# JacdacMicroBitShieldLPEc_113.net
KiCad netlist of a schematic drawn in Altium Designer
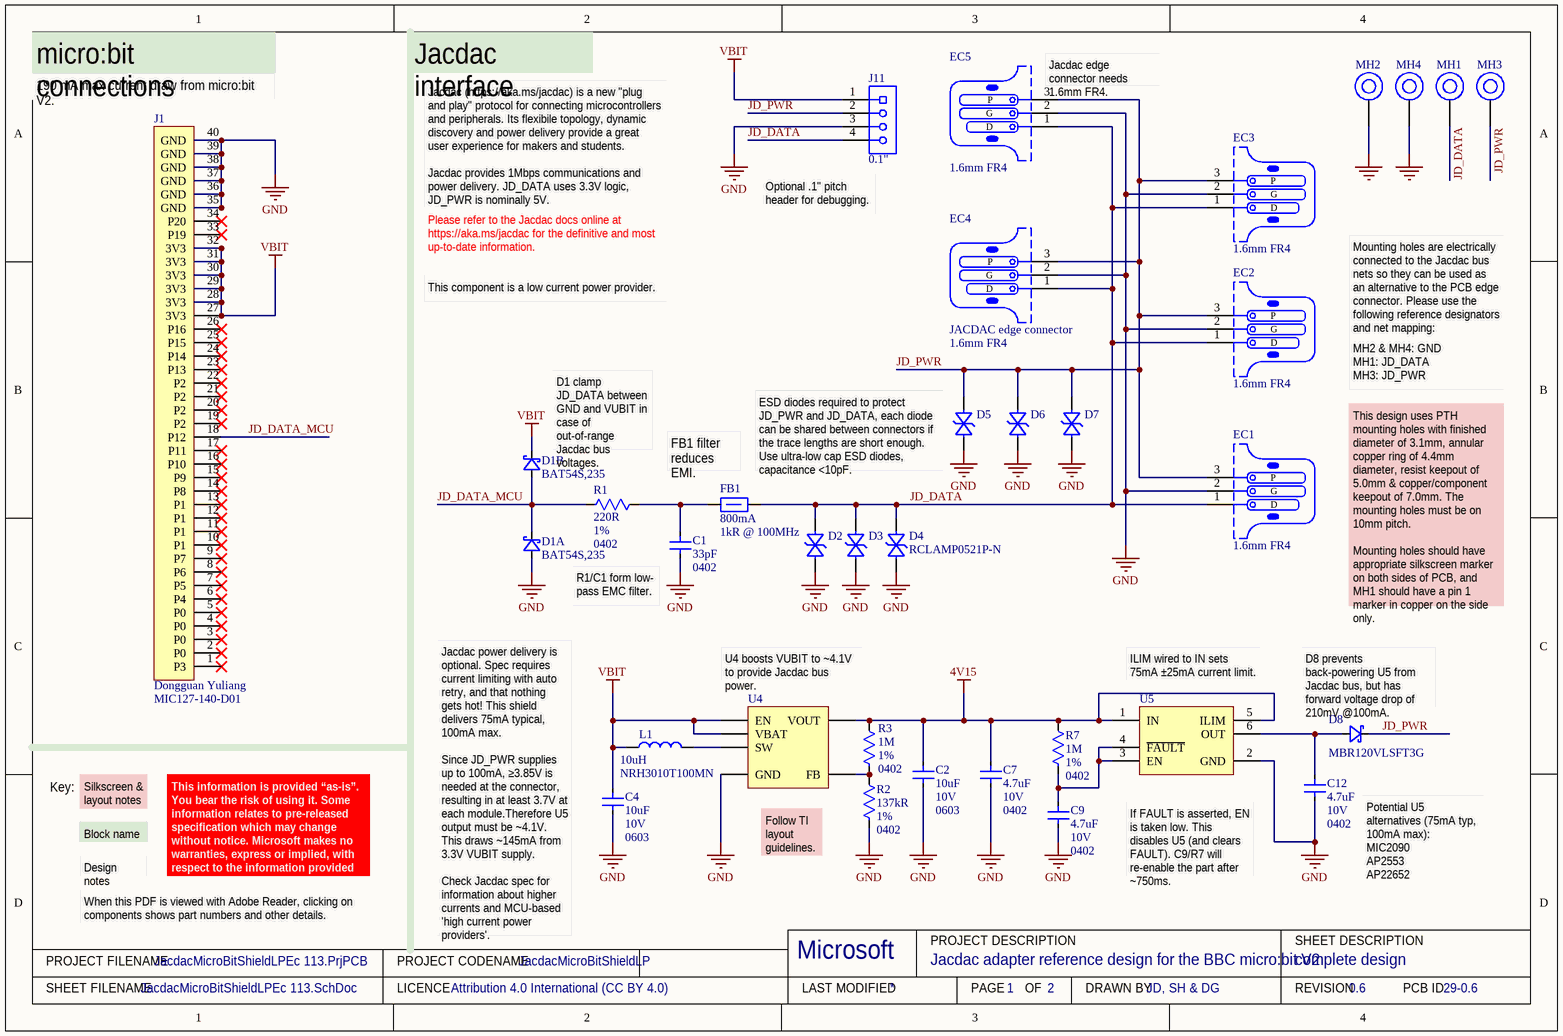
[diagram p0: JacdacMicroBitShieldLPEc 113.SchDoc]

(export (version "E")
  (design (tool "Eeschema 10.0.6"))
  (components
    (comp (ref "C1")
      (value "CL05C330JB51PNC")
      (footprint "C0402_0.55MM - without outline")
      (description "CAP CER 33PF 50V NP0 0402")
      (fields
        (field (name "MANUFACTURER") "Samsung")
        (field (name "TOLERANCE") "5%")
        (field (name "CAPACITANCE") "33pF")
        (field (name "CASE CODE (IMPERIAL)") "0402")
        (field (name "CHECKED") "?")
        (field (name "CREATED") "DG")
      )
      (libsource (lib "Samsung") (part "CL05C330JB51PNC"))
    )
    (comp (ref "C2")
      (value "CL10A106KP8NNNC")
      (footprint "C0603 - without outline")
      (description "CAP CER 10UF 10V X5R 0603")
      (fields
        (field (name "MANUFACTURER") "Samsung")
        (field (name "TOLERANCE") "10%")
        (field (name "CAPACITANCE") "10uF")
        (field (name "VOLTAGE RATING") "10V")
        (field (name "CASE CODE (IMPERIAL)") "0603")
      )
      (libsource (lib "Samsung") (part "CL10A106KP8NNNC"))
    )
    (comp (ref "C4")
      (value "CL10A106KP8NNNC")
      (footprint "C0603 - without outline")
      (description "CAP CER 10UF 10V X5R 0603")
      (fields
        (field (name "MANUFACTURER") "Samsung")
        (field (name "TOLERANCE") "10%")
        (field (name "CAPACITANCE") "10uF")
        (field (name "VOLTAGE RATING") "10V")
        (field (name "CASE CODE (IMPERIAL)") "0603")
      )
      (libsource (lib "Samsung") (part "CL10A106KP8NNNC"))
    )
    (comp (ref "C7")
      (value "CL05A475MP5NRNC")
      (footprint "R0402 - Without outline")
      (description "CAP CER 4.7UF 10V X5R 0402")
      (fields
        (field (name "MANUFACTURER") "Samsung")
        (field (name "TOLERANCE") "20%")
        (field (name "CAPACITANCE") "4.7uF")
        (field (name "VOLTAGE RATING") "10V")
        (field (name "CASE CODE (IMPERIAL)") "0402")
        (field (name "CREATED BY") "D. Gakure")
        (field (name "CHECKED BY") "?")
      )
      (libsource (lib "Samsung") (part "CL05A475MP5NRNC"))
    )
    (comp (ref "C9")
      (value "CL05A475MP5NRNC")
      (footprint "R0402 - Without outline")
      (description "CAP CER 4.7UF 10V X5R 0402")
      (fields
        (field (name "MANUFACTURER") "Samsung")
        (field (name "TOLERANCE") "20%")
        (field (name "CAPACITANCE") "4.7uF")
        (field (name "VOLTAGE RATING") "10V")
        (field (name "CASE CODE (IMPERIAL)") "0402")
        (field (name "CREATED BY") "D. Gakure")
        (field (name "CHECKED BY") "?")
      )
      (libsource (lib "Samsung") (part "CL05A475MP5NRNC"))
    )
    (comp (ref "C12")
      (value "CL05A475MP5NRNC")
      (footprint "R0402 - Without outline")
      (description "CAP CER 4.7UF 10V X5R 0402")
      (fields
        (field (name "MANUFACTURER") "Samsung")
        (field (name "TOLERANCE") "20%")
        (field (name "CAPACITANCE") "4.7uF")
        (field (name "VOLTAGE RATING") "10V")
        (field (name "CASE CODE (IMPERIAL)") "0402")
        (field (name "CREATED BY") "D. Gakure")
        (field (name "CHECKED BY") "?")
      )
      (libsource (lib "Samsung") (part "CL05A475MP5NRNC"))
    )
    (comp (ref "D1")
      (value "BAT54S")
      (footprint "NXP-BAT54S-TO-236AB - without outline")
      (description "DIODE ARRAY SCHOTTKY 30V SOT23")
      (fields (field (name "MANUFACTURER") "Nexperia") (field (name "MANUFACTURER PART NUMBER") "BAT54S,235"))
      (libsource (lib "NXP") (part "BAT54S"))
    )
    (comp (ref "D2")
      (value "RCLAMP0521P-N")
      (footprint "TVS 0402 - L")
      (description "Bidirectional 5V (Max) 6V 16V 3.5A (8/20us) 0402 TVS RoHS")
      (fields
        (field (name "MANUFACTURER") "Born Semiconductor")
        (field (name "CREATED BY") "D Gakure")
        (field (name "CHECKED BY") "?")
      )
      (libsource (lib "BornSemiconductor") (part "RCLAMP0521P-N"))
    )
    (comp (ref "D3")
      (value "RCLAMP0521P-N")
      (footprint "TVS 0402 - L")
      (description "Bidirectional 5V (Max) 6V 16V 3.5A (8/20us) 0402 TVS RoHS")
      (fields
        (field (name "MANUFACTURER") "Born Semiconductor")
        (field (name "CREATED BY") "D Gakure")
        (field (name "CHECKED BY") "?")
      )
      (libsource (lib "BornSemiconductor") (part "RCLAMP0521P-N"))
    )
    (comp (ref "D4")
      (value "RCLAMP0521P-N")
      (footprint "TVS 0402 - L")
      (description "Bidirectional 5V (Max) 6V 16V 3.5A (8/20us) 0402 TVS RoHS")
      (fields
        (field (name "MANUFACTURER") "Born Semiconductor")
        (field (name "MANUFACTURER PART NUMBER") "RCLAMP0521P-N")
        (field (name "CREATED BY") "D Gakure")
        (field (name "CHECKED BY") "?")
      )
      (libsource (lib "BornSemiconductor") (part "RCLAMP0521P-N"))
    )
    (comp (ref "D5")
      (value "RCLAMP0521P-N")
      (footprint "TVS 0402 - L")
      (description "Bidirectional 5V (Max) 6V 16V 3.5A (8/20us) 0402 TVS RoHS")
      (fields
        (field (name "MANUFACTURER") "Born Semiconductor")
        (field (name "CREATED BY") "D Gakure")
        (field (name "CHECKED BY") "?")
      )
      (libsource (lib "BornSemiconductor") (part "RCLAMP0521P-N"))
    )
    (comp (ref "D6")
      (value "RCLAMP0521P-N")
      (footprint "TVS 0402 - L")
      (description "Bidirectional 5V (Max) 6V 16V 3.5A (8/20us) 0402 TVS RoHS")
      (fields
        (field (name "MANUFACTURER") "Born Semiconductor")
        (field (name "CREATED BY") "D Gakure")
        (field (name "CHECKED BY") "?")
      )
      (libsource (lib "BornSemiconductor") (part "RCLAMP0521P-N"))
    )
    (comp (ref "D7")
      (value "RCLAMP0521P-N")
      (footprint "TVS 0402 - L")
      (description "Bidirectional 5V (Max) 6V 16V 3.5A (8/20us) 0402 TVS RoHS")
      (fields
        (field (name "MANUFACTURER") "Born Semiconductor")
        (field (name "CREATED BY") "D Gakure")
        (field (name "CHECKED BY") "?")
      )
      (libsource (lib "BornSemiconductor") (part "RCLAMP0521P-N"))
    )
    (comp (ref "D8")
      (value "MBR120VLSFT3G")
      (footprint "MBR120VLSFT3G")
      (description "DIODE SCHOTTKY 20V 1A SOD123FL")
      (fields
        (field (name "MANUFACTURER") "ON Semiconductor")
        (field (name "MANUFACTURER PART NUMBER") "MBR120VLSFT3G")
      )
      (libsource (lib "OnSemiconductor") (part "MBR120VLSFT3G"))
    )
    (comp (ref "EC1")
      (value "Jacdac edge connector")
      (footprint "JACDAC_edge_connector:JACDAC_EDGE_CONNECTOR_NO_TRACES")
      (description "3 pin jacdac edge connector 1.27mm pitch")
      (fields
        (field (name "MANUFACTURER PART NUMBER") "JACDAC_EDGE_CONNECTOR")
        (field (name "PCB TYPE") "1.6mm FR4")
        (field (name "CHECKED BY") "?")
        (field (name "CREATED BY") "D. Gakure")
      )
      (libsource (lib "generic-con") (part "Jacdac edge connector"))
    )
    (comp (ref "EC2")
      (value "Jacdac edge connector")
      (footprint "JACDAC_edge_connector:JACDAC_EDGE_CONNECTOR_NO_TRACES")
      (description "3 pin jacdac edge connector 1.27mm pitch")
      (fields
        (field (name "MANUFACTURER PART NUMBER") "JACDAC_EDGE_CONNECTOR")
        (field (name "PCB TYPE") "1.6mm FR4")
        (field (name "CHECKED BY") "?")
        (field (name "CREATED BY") "D. Gakure")
      )
      (libsource (lib "generic-con") (part "Jacdac edge connector"))
    )
    (comp (ref "EC3")
      (value "Jacdac edge connector")
      (footprint "JACDAC_edge_connector:JACDAC_EDGE_CONNECTOR_NO_TRACES")
      (description "3 pin jacdac edge connector 1.27mm pitch")
      (fields
        (field (name "MANUFACTURER PART NUMBER") "JACDAC_EDGE_CONNECTOR")
        (field (name "PCB TYPE") "1.6mm FR4")
        (field (name "CHECKED BY") "?")
        (field (name "CREATED BY") "D. Gakure")
      )
      (libsource (lib "generic-con") (part "Jacdac edge connector"))
    )
    (comp (ref "EC4")
      (value "JACDAC edge connector")
      (footprint "JACDAC_edge_connector:JACDAC_EDGE_CONNECTOR_NO_TRACES")
      (description "3 pin jacdac edge connector 1.27mm pitch")
      (fields
        (field (name "MANUFACTURER PART NUMBER") "JACDAC_EDGE_CONNECTOR")
        (field (name "PCB TYPE") "1.6mm FR4")
        (field (name "CHECKED BY") "?")
        (field (name "CREATED BY") "D. Gakure")
      )
      (libsource (lib "") (part "Jacdac edge connector_1"))
    )
    (comp (ref "EC5")
      (value "Jacdac edge connector")
      (footprint "JACDAC_edge_connector:JACDAC_EDGE_CONNECTOR_NO_TRACES")
      (description "3 pin jacdac edge connector 1.27mm pitch")
      (fields
        (field (name "MANUFACTURER PART NUMBER") "JACDAC_EDGE_CONNECTOR")
        (field (name "PCB TYPE") "1.6mm FR4")
        (field (name "CHECKED BY") "?")
        (field (name "CREATED BY") "D. Gakure")
      )
      (libsource (lib "") (part "Jacdac edge connector_1"))
    )
    (comp (ref "FB1")
      (value "TDK MPZ1608S102ATA00")
      (footprint "TDK MPZ1608 0.8mm - without outline")
      (description "0603 1k@100MHz 0.8A chip")
      (fields
        (field (name "TOLERANCE") "25%")
        (field (name "MANUFACTURER") "TDK")
        (field (name "CURRENT RATING") "800mA")
        (field (name "IMPEDANCE") "1kR @ 100MHz")
      )
      (libsource (lib "TDK") (part "TDK MPZ1608S102ATA00"))
    )
    (comp (ref "J1")
      (value "Planar 1x40p 1.27 mm pitch edge connector for the micro:bit")
      (footprint "MIC127-140-D01")
      (description "\"Same plane\" 1x40p 1.27mm Dongguan Yuliang BBC micro:bit edge connector")
      (fields
        (field (name "MANUFACTURER") "Dongguan Yuliang")
        (field (name "MANUFACTURER PART NUMBER") "MIC127-140-D01")
      )
      (libsource (lib "Yuliang") (part "MIC127-140-D01"))
    )
    (comp (ref "J11")
      (value "0.1\"")
      (footprint "Generic 1x4 2.54mm header")
      (description "2.54mm, 4x1 way, vertical, square pin, gold plate")
      (fields
        (field (name "MANUFACTURER") "Multicomp")
        (field (name "MANUFACTURER PART NUMBER") "2211S-04G")
        (field (name "CREATED BY") "HUGHWI")
      )
      (libsource (lib "generic-con") (part "Header Multicomp 2211S-04G-whitesch"))
    )
    (comp (ref "L1")
      (value "NRH3010T100MN")
      (footprint "NRH3010T100MN")
      (fields
        (field (name "TOLERANCE") "20%")
        (field (name "INDUCTANCE") "10uH")
        (field (name "MANUFACTURER") "Taiyo Yuden")
        (field (name "MANUFACTURER PART NUMBER") "NRH3010T100MN")
      )
      (libsource (lib "TaiyoYuden ") (part "NRH3010T100MN"))
    )
    (comp (ref "MH1")
      (value "MH_6.5MMK_4.5MMC_3.0MMD_PTH")
      (footprint "MH_6.5MMK_4.5MMC_3.0MMD_PTH:MH_6.5MMK_4.5MMC_3.0MMD_PTH")
      (description "Mounting Hole 6.5mm keepout, 4.5mm annualar ring and 3.0mm Drill PTH")
      (libsource (lib "generic") (part "MH_6.5MMK_4.5MMC_3.0MMD_PTH"))
    )
    (comp (ref "MH2")
      (value "MH_6.5MMK_4.5MMC_3.0MMD_PTH")
      (footprint "MH_6.5MMK_4.5MMC_3.0MMD_PTH:MH_6.5MMK_4.5MMC_3.0MMD_PTH")
      (description "Mounting Hole 6.5mm keepout, 4.5mm annualar ring and 3.0mm Drill PTH")
      (libsource (lib "generic") (part "MH_6.5MMK_4.5MMC_3.0MMD_PTH"))
    )
    (comp (ref "MH3")
      (value "MH_6.5MMK_4.5MMC_3.0MMD_PTH")
      (footprint "MH_6.5MMK_4.5MMC_3.0MMD_PTH:MH_6.5MMK_4.5MMC_3.0MMD_PTH")
      (description "Mounting Hole 6.5mm keepout, 4.5mm annualar ring and 3.0mm Drill PTH")
      (libsource (lib "generic") (part "MH_6.5MMK_4.5MMC_3.0MMD_PTH"))
    )
    (comp (ref "MH4")
      (value "MH_6.5MMK_4.5MMC_3.0MMD_PTH")
      (footprint "MH_6.5MMK_4.5MMC_3.0MMD_PTH:MH_6.5MMK_4.5MMC_3.0MMD_PTH")
      (description "Mounting Hole 6.5mm keepout, 4.5mm annualar ring and 3.0mm Drill PTH")
      (libsource (lib "generic") (part "MH_6.5MMK_4.5MMC_3.0MMD_PTH"))
    )
    (comp (ref "R1")
      (value "0402WGF2200TCE")
      (footprint "UNIROYAL-0402:R0402 - Without outline")
      (description "RES SMD 220 OHM 1% 1/16W 0402")
      (fields
        (field (name "MANUFACTURER") "Uniroyal Elec")
        (field (name "RESISTANCE") "220R")
        (field (name "TOLERANCE") "1%")
        (field (name "CASE CODE (IMPERIAL)") "0402")
      )
      (libsource (lib "UniroyalElec") (part "0402WGF2200TCE"))
    )
    (comp (ref "R2")
      (value "RC0402FR-07137KL")
      (footprint "R0402 - Without outline")
      (description "RES SMD 137K OHM 1% 1/16W 0402")
      (fields
        (field (name "MANUFACTURER") "Yageo")
        (field (name "RESISTANCE") "137kR")
        (field (name "TOLERANCE") "1%")
        (field (name "CASE CODE (IMPERIAL)") "0402")
      )
      (libsource (lib "Yageo") (part "RC0402FR-07137KL"))
    )
    (comp (ref "R3")
      (value "0402WGF1004TCE")
      (footprint "UNIROYAL-0402:R0402 - Without outline")
      (description "RES SMD 1M OHM 1% 1/16W 0402")
      (fields
        (field (name "MANUFACTURER") "Uniroyal Elec")
        (field (name "RESISTANCE") "1M")
        (field (name "TOLERANCE") "1%")
        (field (name "CASE CODE (IMPERIAL)") "0402")
      )
      (libsource (lib "UniroyalElec") (part "0402WGF1004TCE"))
    )
    (comp (ref "R7")
      (value "0402WGF1004TCE")
      (footprint "UNIROYAL-0402:R0402 - Without outline")
      (description "RES SMD 1M OHM 1% 1/16W 0402")
      (fields
        (field (name "MANUFACTURER") "Uniroyal Elec")
        (field (name "RESISTANCE") "1M")
        (field (name "TOLERANCE") "1%")
        (field (name "CASE CODE (IMPERIAL)") "0402")
      )
      (libsource (lib "UniroyalElec") (part "0402WGF1004TCE"))
    )
    (comp (ref "U4")
      (value "TLV61220")
      (footprint "TI-TLV61220 - without_outline")
      (description "IC REG BST ADJ 0.22A SYNC SOT23")
      (fields (field (name "MANUFACTURER PART NUMBER") "TLV61220DBVR"))
      (libsource (lib "TexasInstruments") (part "TLV61220"))
    )
    (comp (ref "U5")
      (value "TPS2553DBVR")
      (footprint "TI-TPS2553 - without_outline")
      (libsource (lib "TexasInstruments") (part "TPS2553DBVR"))
    )
  )
  (nets
    (net (code "1") (name "/JD_DATA") (class "Default")
      (node (ref "D2") (pin "1") (pinfunction "K_1") (pintype "passive"))
      (node (ref "D3") (pin "1") (pinfunction "K_1") (pintype "passive"))
      (node (ref "D4") (pin "1") (pinfunction "K_1") (pintype "passive"))
      (node (ref "EC1") (pin "1") (pinfunction "D_1") (pintype "passive"))
      (node (ref "EC2") (pin "1") (pinfunction "D_1") (pintype "passive"))
      (node (ref "EC3") (pin "1") (pinfunction "D_1") (pintype "passive"))
      (node (ref "EC4") (pin "1") (pinfunction "D_1") (pintype "passive"))
      (node (ref "EC5") (pin "1") (pinfunction "D_1") (pintype "passive"))
      (node (ref "FB1") (pin "1") (pinfunction "1_1") (pintype "passive"))
      (node (ref "J11") (pin "4") (pinfunction "4_4") (pintype "passive"))
      (node (ref "MH1") (pin "1") (pinfunction "1_1") (pintype "passive"))
    )
    (net (code "2") (name "/JD_DATA_MCU") (class "Default")
      (node (ref "D1") (pin "3") (pinfunction "K_3") (pintype "passive"))
      (node (ref "J1") (pin "18") (pinfunction "P12_18") (pintype "passive"))
      (node (ref "R1") (pin "1") (pinfunction "1_1") (pintype "passive"))
    )
    (net (code "3") (name "/JD_PWR") (class "Default")
      (node (ref "D5") (pin "1") (pinfunction "K_1") (pintype "passive"))
      (node (ref "D6") (pin "1") (pinfunction "K_1") (pintype "passive"))
      (node (ref "D7") (pin "1") (pinfunction "K_1") (pintype "passive"))
      (node (ref "D8") (pin "1") (pinfunction "K_1") (pintype "passive"))
      (node (ref "EC1") (pin "3") (pinfunction "P_3") (pintype "passive"))
      (node (ref "EC2") (pin "3") (pinfunction "P_3") (pintype "passive"))
      (node (ref "EC3") (pin "3") (pinfunction "P_3") (pintype "passive"))
      (node (ref "EC4") (pin "3") (pinfunction "P_3") (pintype "passive"))
      (node (ref "EC5") (pin "3") (pinfunction "P_3") (pintype "passive"))
      (node (ref "J11") (pin "2") (pinfunction "2_2") (pintype "passive"))
      (node (ref "MH3") (pin "1") (pinfunction "1_1") (pintype "passive"))
    )
    (net (code "4") (name "4V15") (class "Default")
      (node (ref "C2") (pin "2") (pinfunction "2_2") (pintype "passive"))
      (node (ref "C7") (pin "2") (pinfunction "2_2") (pintype "passive"))
      (node (ref "R3") (pin "2") (pinfunction "2_2") (pintype "passive"))
      (node (ref "R7") (pin "2") (pinfunction "2_2") (pintype "passive"))
      (node (ref "U4") (pin "5") (pinfunction "VOUT_5") (pintype "passive"))
      (node (ref "U5") (pin "1") (pinfunction "IN_1") (pintype "passive"))
      (node (ref "U5") (pin "5") (pinfunction "ILIM_5") (pintype "passive"))
    )
    (net (code "5") (name "GND") (class "Default")
      (node (ref "C1") (pin "1") (pinfunction "1_1") (pintype "passive"))
      (node (ref "C12") (pin "1") (pinfunction "1_1") (pintype "passive"))
      (node (ref "C2") (pin "1") (pinfunction "1_1") (pintype "passive"))
      (node (ref "C4") (pin "1") (pinfunction "1_1") (pintype "passive"))
      (node (ref "C7") (pin "1") (pinfunction "1_1") (pintype "passive"))
      (node (ref "C9") (pin "1") (pinfunction "1_1") (pintype "passive"))
      (node (ref "D1") (pin "1") (pinfunction "A_1") (pintype "passive"))
      (node (ref "D2") (pin "2") (pinfunction "A_2") (pintype "passive"))
      (node (ref "D3") (pin "2") (pinfunction "A_2") (pintype "passive"))
      (node (ref "D4") (pin "2") (pinfunction "A_2") (pintype "passive"))
      (node (ref "D5") (pin "2") (pinfunction "A_2") (pintype "passive"))
      (node (ref "D6") (pin "2") (pinfunction "A_2") (pintype "passive"))
      (node (ref "D7") (pin "2") (pinfunction "A_2") (pintype "passive"))
      (node (ref "EC1") (pin "2") (pinfunction "G_2") (pintype "passive"))
      (node (ref "EC2") (pin "2") (pinfunction "G_2") (pintype "passive"))
      (node (ref "EC3") (pin "2") (pinfunction "G_2") (pintype "passive"))
      (node (ref "EC4") (pin "2") (pinfunction "G_2") (pintype "passive"))
      (node (ref "EC5") (pin "2") (pinfunction "G_2") (pintype "passive"))
      (node (ref "J1") (pin "35") (pinfunction "GND_35") (pintype "passive"))
      (node (ref "J1") (pin "36") (pinfunction "GND_36") (pintype "passive"))
      (node (ref "J1") (pin "37") (pinfunction "GND_37") (pintype "passive"))
      (node (ref "J1") (pin "38") (pinfunction "GND_38") (pintype "passive"))
      (node (ref "J1") (pin "39") (pinfunction "GND_39") (pintype "passive"))
      (node (ref "J1") (pin "40") (pinfunction "GND_40") (pintype "passive"))
      (node (ref "J11") (pin "3") (pinfunction "3_3") (pintype "passive"))
      (node (ref "MH2") (pin "1") (pinfunction "1_1") (pintype "passive"))
      (node (ref "MH4") (pin "1") (pinfunction "1_1") (pintype "passive"))
      (node (ref "R2") (pin "1") (pinfunction "1_1") (pintype "passive"))
      (node (ref "U4") (pin "2") (pinfunction "GND_2") (pintype "passive"))
      (node (ref "U5") (pin "2") (pinfunction "GND_2") (pintype "passive"))
    )
    (net (code "6") (name "Net-(C1-Pad2)") (class "Default")
      (node (ref "C1") (pin "2") (pinfunction "2_2") (pintype "passive"))
      (node (ref "FB1") (pin "2") (pinfunction "2_2") (pintype "passive"))
      (node (ref "R1") (pin "2") (pinfunction "2_2") (pintype "passive"))
    )
    (net (code "7") (name "Net-(D8-A)") (class "Default")
      (node (ref "C12") (pin "2") (pinfunction "2_2") (pintype "passive"))
      (node (ref "D8") (pin "2") (pinfunction "A_2") (pintype "passive"))
      (node (ref "U5") (pin "6") (pinfunction "OUT_6") (pintype "passive"))
    )
    (net (code "8") (name "Net-(U4-FB)") (class "Default")
      (node (ref "R2") (pin "2") (pinfunction "2_2") (pintype "passive"))
      (node (ref "R3") (pin "1") (pinfunction "1_1") (pintype "passive"))
      (node (ref "U4") (pin "4") (pinfunction "FB_4") (pintype "passive"))
    )
    (net (code "9") (name "Net-(U4-SW)") (class "Default")
      (node (ref "L1") (pin "2") (pinfunction "2_2") (pintype "passive"))
      (node (ref "U4") (pin "1") (pinfunction "SW_1") (pintype "passive"))
    )
    (net (code "10") (name "Net-(U5-EN)") (class "Default")
      (node (ref "C9") (pin "2") (pinfunction "2_2") (pintype "passive"))
      (node (ref "R7") (pin "1") (pinfunction "1_1") (pintype "passive"))
      (node (ref "U5") (pin "3") (pinfunction "EN_3") (pintype "passive"))
      (node (ref "U5") (pin "4") (pinfunction "~{FAULT}_4") (pintype "passive"))
    )
    (net (code "11") (name "VBIT") (class "Default")
      (node (ref "C4") (pin "2") (pinfunction "2_2") (pintype "passive"))
      (node (ref "D1") (pin "2") (pinfunction "K_2") (pintype "passive"))
      (node (ref "J1") (pin "27") (pinfunction "3V3_27") (pintype "passive"))
      (node (ref "J1") (pin "28") (pinfunction "3V3_28") (pintype "passive"))
      (node (ref "J1") (pin "29") (pinfunction "3V3_29") (pintype "passive"))
      (node (ref "J1") (pin "30") (pinfunction "3V3_30") (pintype "passive"))
      (node (ref "J1") (pin "31") (pinfunction "3V3_31") (pintype "passive"))
      (node (ref "J1") (pin "32") (pinfunction "3V3_32") (pintype "passive"))
      (node (ref "J11") (pin "1") (pinfunction "1_1") (pintype "passive"))
      (node (ref "L1") (pin "1") (pinfunction "1_1") (pintype "passive"))
      (node (ref "U4") (pin "3") (pinfunction "EN_3") (pintype "passive"))
      (node (ref "U4") (pin "6") (pinfunction "VBAT_6") (pintype "passive"))
    )
    (net (code "12") (name "unconnected-(J1-P0-Pad2)") (class "Default")
      (node (ref "J1") (pin "2") (pinfunction "P0_2") (pintype "passive+no_connect"))
    )
    (net (code "13") (name "unconnected-(J1-P0-Pad3)") (class "Default")
      (node (ref "J1") (pin "3") (pinfunction "P0_3") (pintype "passive+no_connect"))
    )
    (net (code "14") (name "unconnected-(J1-P0-Pad4)") (class "Default")
      (node (ref "J1") (pin "4") (pinfunction "P0_4") (pintype "passive+no_connect"))
    )
    (net (code "15") (name "unconnected-(J1-P0-Pad5)") (class "Default")
      (node (ref "J1") (pin "5") (pinfunction "P0_5") (pintype "passive+no_connect"))
    )
    (net (code "16") (name "unconnected-(J1-P1-Pad10)") (class "Default")
      (node (ref "J1") (pin "10") (pinfunction "P1_10") (pintype "passive+no_connect"))
    )
    (net (code "17") (name "unconnected-(J1-P1-Pad11)") (class "Default")
      (node (ref "J1") (pin "11") (pinfunction "P1_11") (pintype "passive+no_connect"))
    )
    (net (code "18") (name "unconnected-(J1-P1-Pad12)") (class "Default")
      (node (ref "J1") (pin "12") (pinfunction "P1_12") (pintype "passive+no_connect"))
    )
    (net (code "19") (name "unconnected-(J1-P1-Pad13)") (class "Default")
      (node (ref "J1") (pin "13") (pinfunction "P1_13") (pintype "passive+no_connect"))
    )
    (net (code "20") (name "unconnected-(J1-P2-Pad19)") (class "Default")
      (node (ref "J1") (pin "19") (pinfunction "P2_19") (pintype "passive+no_connect"))
    )
    (net (code "21") (name "unconnected-(J1-P2-Pad20)") (class "Default")
      (node (ref "J1") (pin "20") (pinfunction "P2_20") (pintype "passive+no_connect"))
    )
    (net (code "22") (name "unconnected-(J1-P2-Pad21)") (class "Default")
      (node (ref "J1") (pin "21") (pinfunction "P2_21") (pintype "passive+no_connect"))
    )
    (net (code "23") (name "unconnected-(J1-P2-Pad22)") (class "Default")
      (node (ref "J1") (pin "22") (pinfunction "P2_22") (pintype "passive+no_connect"))
    )
    (net (code "24") (name "unconnected-(J1-P3-Pad1)") (class "Default")
      (node (ref "J1") (pin "1") (pinfunction "P3_1") (pintype "passive+no_connect"))
    )
    (net (code "25") (name "unconnected-(J1-P4-Pad6)") (class "Default")
      (node (ref "J1") (pin "6") (pinfunction "P4_6") (pintype "passive+no_connect"))
    )
    (net (code "26") (name "unconnected-(J1-P5-Pad7)") (class "Default")
      (node (ref "J1") (pin "7") (pinfunction "P5_7") (pintype "passive+no_connect"))
    )
    (net (code "27") (name "unconnected-(J1-P6-Pad8)") (class "Default")
      (node (ref "J1") (pin "8") (pinfunction "P6_8") (pintype "passive+no_connect"))
    )
    (net (code "28") (name "unconnected-(J1-P7-Pad9)") (class "Default")
      (node (ref "J1") (pin "9") (pinfunction "P7_9") (pintype "passive+no_connect"))
    )
    (net (code "29") (name "unconnected-(J1-P8-Pad14)") (class "Default")
      (node (ref "J1") (pin "14") (pinfunction "P8_14") (pintype "passive+no_connect"))
    )
    (net (code "30") (name "unconnected-(J1-P9-Pad15)") (class "Default")
      (node (ref "J1") (pin "15") (pinfunction "P9_15") (pintype "passive+no_connect"))
    )
    (net (code "31") (name "unconnected-(J1-P10-Pad16)") (class "Default")
      (node (ref "J1") (pin "16") (pinfunction "P10_16") (pintype "passive+no_connect"))
    )
    (net (code "32") (name "unconnected-(J1-P11-Pad17)") (class "Default")
      (node (ref "J1") (pin "17") (pinfunction "P11_17") (pintype "passive+no_connect"))
    )
    (net (code "33") (name "unconnected-(J1-P13-Pad23)") (class "Default")
      (node (ref "J1") (pin "23") (pinfunction "P13_23") (pintype "passive+no_connect"))
    )
    (net (code "34") (name "unconnected-(J1-P14-Pad24)") (class "Default")
      (node (ref "J1") (pin "24") (pinfunction "P14_24") (pintype "passive+no_connect"))
    )
    (net (code "35") (name "unconnected-(J1-P15-Pad25)") (class "Default")
      (node (ref "J1") (pin "25") (pinfunction "P15_25") (pintype "passive+no_connect"))
    )
    (net (code "36") (name "unconnected-(J1-P16-Pad26)") (class "Default")
      (node (ref "J1") (pin "26") (pinfunction "P16_26") (pintype "passive+no_connect"))
    )
    (net (code "37") (name "unconnected-(J1-P19-Pad33)") (class "Default")
      (node (ref "J1") (pin "33") (pinfunction "P19_33") (pintype "passive+no_connect"))
    )
    (net (code "38") (name "unconnected-(J1-P20-Pad34)") (class "Default")
      (node (ref "J1") (pin "34") (pinfunction "P20_34") (pintype "passive+no_connect"))
    )
  )
)
